# mostek-h.net
KiCad netlist of a schematic drawn in EAGLE
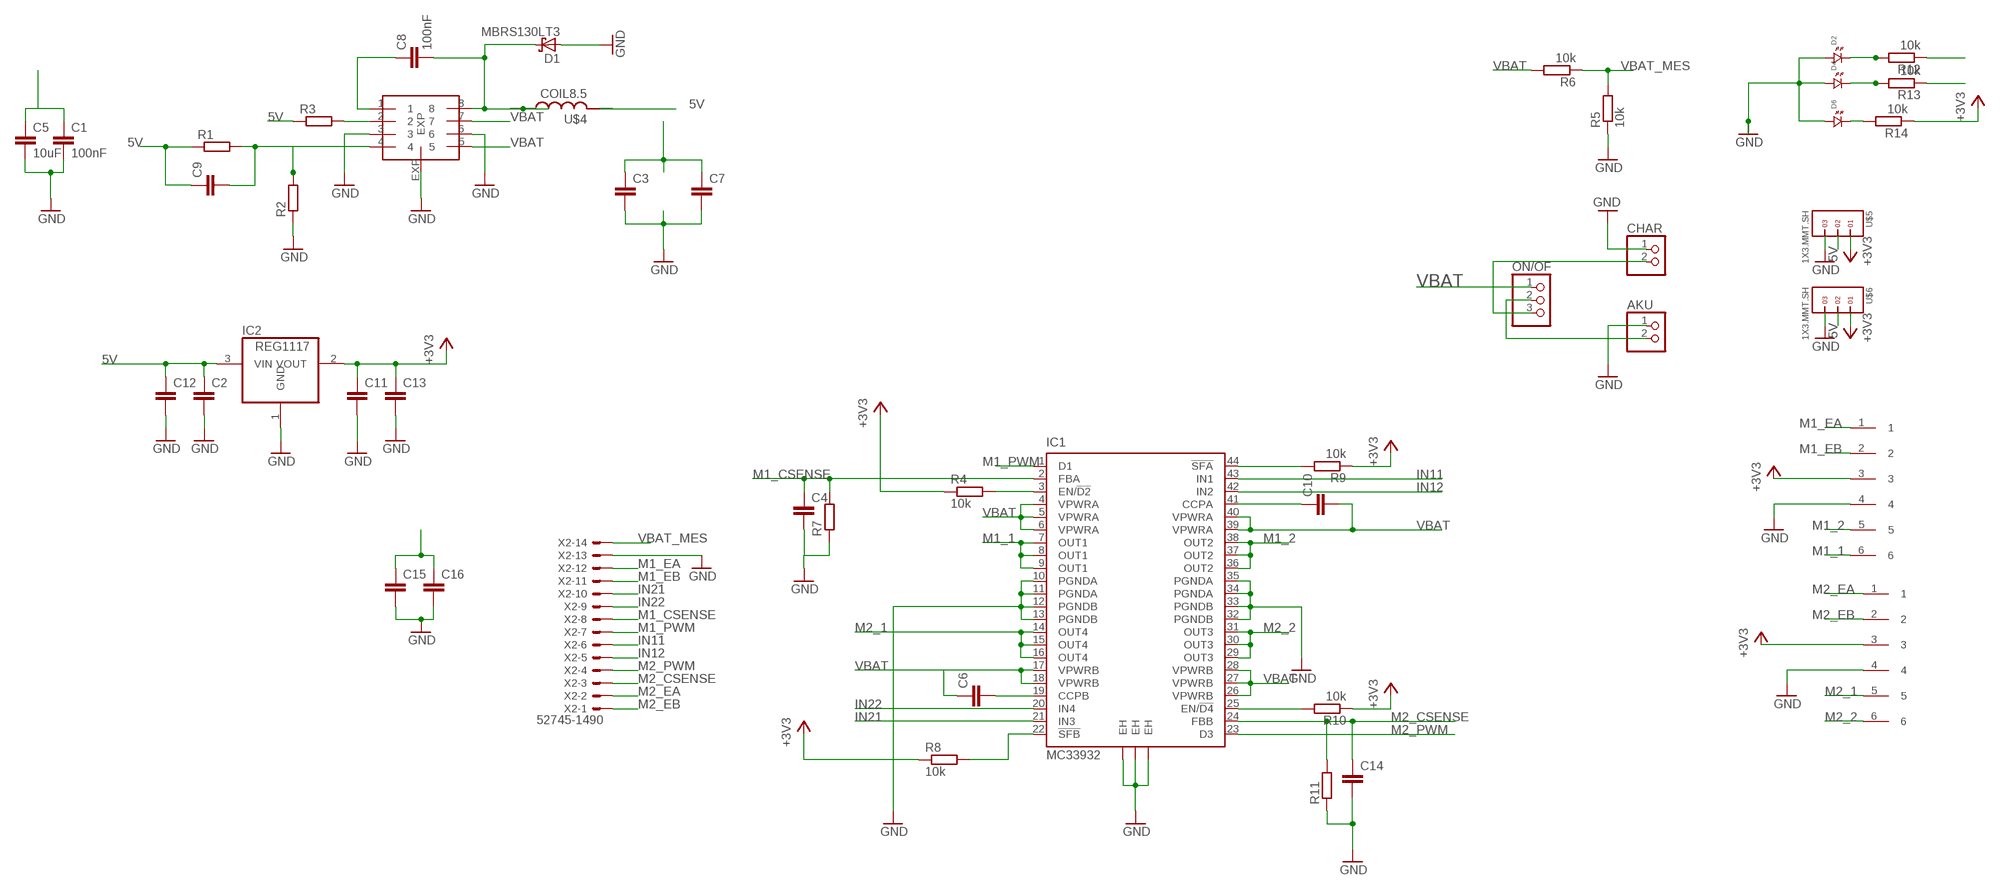
[diagram p0: schematic, sheet 1]

(export (version "E")
  (design (tool "Eeschema 10.0.6"))
  (components
    (comp (ref "AKU")
      (value "PINHD-1X2/90")
      (footprint "eagle-import:1X02_90")
      (libsource (lib "eagle-import") (part "PINHD-1X2/90"))
    )
    (comp (ref "C1")
      (value "100nF")
      (footprint "eagle-import:C1210K")
      (libsource (lib "eagle-import") (part "C-EUC1210K"))
    )
    (comp (ref "C2")
      (value "C-EUC0805")
      (footprint "eagle-import:C0805")
      (libsource (lib "eagle-import") (part "C-EUC0805"))
    )
    (comp (ref "C3")
      (value "C-EUC1210K")
      (footprint "eagle-import:C1210K")
      (libsource (lib "eagle-import") (part "C-EUC1210K"))
    )
    (comp (ref "C4")
      (value "C-EUC0603")
      (footprint "eagle-import:C0603")
      (libsource (lib "eagle-import") (part "C-EUC0603"))
    )
    (comp (ref "C5")
      (value "10uF")
      (footprint "eagle-import:C0603")
      (libsource (lib "eagle-import") (part "C-EUC0603"))
    )
    (comp (ref "C6")
      (value "C-EUC0805")
      (footprint "eagle-import:C0805")
      (libsource (lib "eagle-import") (part "C-EUC0805"))
    )
    (comp (ref "C7")
      (value "C-EUC0603")
      (footprint "eagle-import:C0603")
      (libsource (lib "eagle-import") (part "C-EUC0603"))
    )
    (comp (ref "C8")
      (value "100nF")
      (footprint "eagle-import:C0603")
      (libsource (lib "eagle-import") (part "C-EUC0603"))
    )
    (comp (ref "C9")
      (value "C-EUC0603")
      (footprint "eagle-import:C0603")
      (libsource (lib "eagle-import") (part "C-EUC0603"))
    )
    (comp (ref "C10")
      (value "C-EUC0805")
      (footprint "eagle-import:C0805")
      (libsource (lib "eagle-import") (part "C-EUC0805"))
    )
    (comp (ref "C11")
      (value "C-EUC0805")
      (footprint "eagle-import:C0805")
      (libsource (lib "eagle-import") (part "C-EUC0805"))
    )
    (comp (ref "C12")
      (value "C-EUC1210")
      (footprint "eagle-import:C1210")
      (libsource (lib "eagle-import") (part "C-EUC1210"))
    )
    (comp (ref "C13")
      (value "C-EUC1210")
      (footprint "eagle-import:C1210")
      (libsource (lib "eagle-import") (part "C-EUC1210"))
    )
    (comp (ref "C14")
      (value "C-EUC0603")
      (footprint "eagle-import:C0603")
      (libsource (lib "eagle-import") (part "C-EUC0603"))
    )
    (comp (ref "C15")
      (value "C-EUC1210K")
      (footprint "eagle-import:C1210K")
      (libsource (lib "eagle-import") (part "C-EUC1210K"))
    )
    (comp (ref "C16")
      (value "C-EUC0603")
      (footprint "eagle-import:C0603")
      (libsource (lib "eagle-import") (part "C-EUC0603"))
    )
    (comp (ref "CHAR")
      (value "PINHD-1X2/90")
      (footprint "eagle-import:1X02_90")
      (libsource (lib "eagle-import") (part "PINHD-1X2/90"))
    )
    (comp (ref "D1")
      (value "MBRS130LT3")
      (footprint "eagle-import:SMB")
      (libsource (lib "eagle-import") (part "MBRS130LT3"))
    )
    (comp (ref "D2")
      (value "LED.0805")
      (footprint "eagle-import:0805.LED")
      (libsource (lib "eagle-import") (part "LED.0805"))
    )
    (comp (ref "D4")
      (value "LED.0805")
      (footprint "eagle-import:0805.LED")
      (libsource (lib "eagle-import") (part "LED.0805"))
    )
    (comp (ref "D6")
      (value "LED.0805")
      (footprint "eagle-import:0805.LED")
      (libsource (lib "eagle-import") (part "LED.0805"))
    )
    (comp (ref "IC1")
      (value "MC33932")
      (footprint "eagle-import:HSOP44")
      (fields (field (name "MPN") "MC33932VW"))
      (libsource (lib "eagle-import") (part "MC33932"))
    )
    (comp (ref "IC2")
      (value "REG1117")
      (footprint "eagle-import:SOT223")
      (libsource (lib "eagle-import") (part "REG1117"))
    )
    (comp (ref "ON/OF")
      (value "PINHD-1X3/90")
      (footprint "eagle-import:1X03_90")
      (libsource (lib "eagle-import") (part "PINHD-1X3/90"))
    )
    (comp (ref "R1")
      (value "R-EU_R0603")
      (footprint "eagle-import:R0603")
      (libsource (lib "eagle-import") (part "R-EU_R0603"))
    )
    (comp (ref "R2")
      (value "R-EU_R0603")
      (footprint "eagle-import:R0603")
      (libsource (lib "eagle-import") (part "R-EU_R0603"))
    )
    (comp (ref "R3")
      (value "R-EU_R0603")
      (footprint "eagle-import:R0603")
      (libsource (lib "eagle-import") (part "R-EU_R0603"))
    )
    (comp (ref "R4")
      (value "10k")
      (footprint "eagle-import:R0603")
      (libsource (lib "eagle-import") (part "R-EU_R0603"))
    )
    (comp (ref "R5")
      (value "10k")
      (footprint "eagle-import:R0603")
      (libsource (lib "eagle-import") (part "R-EU_R0603"))
    )
    (comp (ref "R6")
      (value "10k")
      (footprint "eagle-import:R0603")
      (libsource (lib "eagle-import") (part "R-EU_R0603"))
    )
    (comp (ref "R7")
      (value "R-EU_R0603")
      (footprint "eagle-import:R0603")
      (libsource (lib "eagle-import") (part "R-EU_R0603"))
    )
    (comp (ref "R8")
      (value "10k")
      (footprint "eagle-import:R0603")
      (libsource (lib "eagle-import") (part "R-EU_R0603"))
    )
    (comp (ref "R9")
      (value "10k")
      (footprint "eagle-import:R0603")
      (libsource (lib "eagle-import") (part "R-EU_R0603"))
    )
    (comp (ref "R10")
      (value "10k")
      (footprint "eagle-import:R0603")
      (libsource (lib "eagle-import") (part "R-EU_R0603"))
    )
    (comp (ref "R11")
      (value "R-EU_R0603")
      (footprint "eagle-import:R0603")
      (libsource (lib "eagle-import") (part "R-EU_R0603"))
    )
    (comp (ref "R12")
      (value "10k")
      (footprint "eagle-import:R0603")
      (libsource (lib "eagle-import") (part "R-EU_R0603"))
    )
    (comp (ref "R13")
      (value "10k")
      (footprint "eagle-import:R0603")
      (libsource (lib "eagle-import") (part "R-EU_R0603"))
    )
    (comp (ref "R14")
      (value "10k")
      (footprint "eagle-import:R0603")
      (libsource (lib "eagle-import") (part "R-EU_R0603"))
    )
    (comp (ref "U$1")
      (value "PAD_SMD_6X1")
      (footprint "eagle-import:SMD_6X1")
      (libsource (lib "eagle-import") (part "PAD_SMD_6X1"))
    )
    (comp (ref "U$2")
      (value "PAD_SMD_6X1")
      (footprint "eagle-import:SMD_6X1")
      (libsource (lib "eagle-import") (part "PAD_SMD_6X1"))
    )
    (comp (ref "U$3")
      (value "ST1S14")
      (footprint "eagle-import:HSOP8")
      (libsource (lib "eagle-import") (part "ST1S14"))
    )
    (comp (ref "U$4")
      (value "COIL8.5")
      (footprint "eagle-import:COIL1")
      (libsource (lib "eagle-import") (part "COIL8.5"))
    )
    (comp (ref "U$5")
      (value "1X3.MMT.SH")
      (footprint "eagle-import:1X3_MMT.103.01.X.SH")
      (libsource (lib "eagle-import") (part "1X3.MMT.SH"))
    )
    (comp (ref "U$6")
      (value "1X3.MMT.SH")
      (footprint "eagle-import:1X3_MMT.103.01.X.SH")
      (libsource (lib "eagle-import") (part "1X3.MMT.SH"))
    )
    (comp (ref "X2")
      (value "52745-1490")
      (footprint "eagle-import:52745-1490")
      (fields (field (name "MF") "WALDOM/MOLEX"))
      (libsource (lib "eagle-import") (part "52745-1490"))
    )
  )
  (nets
    (net (code "1") (name "+3V3") (class "Default")
      (node (ref "C11") (pin "1") (pinfunction "1_1") (pintype "passive"))
      (node (ref "C13") (pin "1") (pinfunction "1_1") (pintype "passive"))
      (node (ref "IC2") (pin "2") (pinfunction "VOUT_2") (pintype "output"))
      (node (ref "R10") (pin "1") (pinfunction "1_1") (pintype "passive"))
      (node (ref "R14") (pin "1") (pinfunction "1_1") (pintype "passive"))
      (node (ref "R4") (pin "1") (pinfunction "1_1") (pintype "passive"))
      (node (ref "R8") (pin "1") (pinfunction "1_1") (pintype "passive"))
      (node (ref "R9") (pin "1") (pinfunction "1_1") (pintype "passive"))
      (node (ref "U$1") (pin "3") (pinfunction "3_3") (pintype "bidirectional"))
      (node (ref "U$2") (pin "3") (pinfunction "3_3") (pintype "bidirectional"))
      (node (ref "U$5") (pin "1") (pinfunction "1_1") (pintype "bidirectional"))
      (node (ref "U$6") (pin "1") (pinfunction "1_1") (pintype "bidirectional"))
    )
    (net (code "2") (name "/5V") (class "Default")
      (node (ref "C12") (pin "1") (pinfunction "1_1") (pintype "passive"))
      (node (ref "C2") (pin "1") (pinfunction "1_1") (pintype "passive"))
      (node (ref "C3") (pin "1") (pinfunction "1_1") (pintype "passive"))
      (node (ref "C7") (pin "1") (pinfunction "1_1") (pintype "passive"))
      (node (ref "C9") (pin "1") (pinfunction "1_1") (pintype "passive"))
      (node (ref "IC2") (pin "3") (pinfunction "VIN_3") (pintype "input"))
      (node (ref "R1") (pin "1") (pinfunction "1_1") (pintype "passive"))
      (node (ref "R13") (pin "1") (pinfunction "1_1") (pintype "passive"))
      (node (ref "R3") (pin "1") (pinfunction "1_1") (pintype "passive"))
      (node (ref "U$4") (pin "2") (pinfunction "2_2") (pintype "passive"))
      (node (ref "U$5") (pin "2") (pinfunction "2_2") (pintype "bidirectional"))
      (node (ref "U$6") (pin "2") (pinfunction "2_2") (pintype "bidirectional"))
    )
    (net (code "3") (name "/IN11") (class "Default")
      (node (ref "IC1") (pin "43") (pinfunction "IN1_43") (pintype "input"))
      (node (ref "X2") (pin "6") (pinfunction "S_6") (pintype "passive"))
    )
    (net (code "4") (name "/IN12") (class "Default")
      (node (ref "IC1") (pin "42") (pinfunction "IN2_42") (pintype "input"))
      (node (ref "X2") (pin "5") (pinfunction "S_5") (pintype "passive"))
    )
    (net (code "5") (name "/IN21") (class "Default")
      (node (ref "IC1") (pin "21") (pinfunction "IN3_21") (pintype "input"))
      (node (ref "X2") (pin "10") (pinfunction "S_10") (pintype "passive"))
    )
    (net (code "6") (name "/IN22") (class "Default")
      (node (ref "IC1") (pin "20") (pinfunction "IN4_20") (pintype "input"))
      (node (ref "X2") (pin "9") (pinfunction "S_9") (pintype "passive"))
    )
    (net (code "7") (name "/M1_1") (class "Default")
      (node (ref "IC1") (pin "7") (pinfunction "OUT1_7") (pintype "output"))
      (node (ref "IC1") (pin "8") (pinfunction "OUT1_8") (pintype "passive"))
      (node (ref "IC1") (pin "9") (pinfunction "OUT1_9") (pintype "passive"))
      (node (ref "U$1") (pin "6") (pinfunction "6_6") (pintype "bidirectional"))
    )
    (net (code "8") (name "/M1_2") (class "Default")
      (node (ref "IC1") (pin "36") (pinfunction "OUT2_36") (pintype "output"))
      (node (ref "IC1") (pin "37") (pinfunction "OUT2_37") (pintype "passive"))
      (node (ref "IC1") (pin "38") (pinfunction "OUT2_38") (pintype "passive"))
      (node (ref "U$1") (pin "5") (pinfunction "5_5") (pintype "bidirectional"))
    )
    (net (code "9") (name "/M1_CSENSE") (class "Default")
      (node (ref "C4") (pin "1") (pinfunction "1_1") (pintype "passive"))
      (node (ref "IC1") (pin "2") (pinfunction "FBA_2") (pintype "output"))
      (node (ref "R7") (pin "2") (pinfunction "2_2") (pintype "passive"))
      (node (ref "X2") (pin "8") (pinfunction "S_8") (pintype "passive"))
    )
    (net (code "10") (name "/M1_EA") (class "Default")
      (node (ref "U$1") (pin "1") (pinfunction "1_1") (pintype "bidirectional"))
      (node (ref "X2") (pin "12") (pinfunction "S_12") (pintype "passive"))
    )
    (net (code "11") (name "/M1_EB") (class "Default")
      (node (ref "U$1") (pin "2") (pinfunction "2_2") (pintype "bidirectional"))
      (node (ref "X2") (pin "11") (pinfunction "S_11") (pintype "passive"))
    )
    (net (code "12") (name "/M1_PWM") (class "Default")
      (node (ref "IC1") (pin "1") (pinfunction "D1_1") (pintype "input"))
      (node (ref "X2") (pin "7") (pinfunction "S_7") (pintype "passive"))
    )
    (net (code "13") (name "/M2_1") (class "Default")
      (node (ref "IC1") (pin "14") (pinfunction "OUT4_14") (pintype "output"))
      (node (ref "IC1") (pin "15") (pinfunction "OUT4_15") (pintype "passive"))
      (node (ref "IC1") (pin "16") (pinfunction "OUT4_16") (pintype "passive"))
      (node (ref "U$2") (pin "5") (pinfunction "5_5") (pintype "bidirectional"))
    )
    (net (code "14") (name "/M2_2") (class "Default")
      (node (ref "IC1") (pin "29") (pinfunction "OUT3_29") (pintype "output"))
      (node (ref "IC1") (pin "30") (pinfunction "OUT3_30") (pintype "passive"))
      (node (ref "IC1") (pin "31") (pinfunction "OUT3_31") (pintype "passive"))
      (node (ref "U$2") (pin "6") (pinfunction "6_6") (pintype "bidirectional"))
    )
    (net (code "15") (name "/M2_CSENSE") (class "Default")
      (node (ref "C14") (pin "1") (pinfunction "1_1") (pintype "passive"))
      (node (ref "IC1") (pin "24") (pinfunction "FBB_24") (pintype "output"))
      (node (ref "R11") (pin "2") (pinfunction "2_2") (pintype "passive"))
      (node (ref "X2") (pin "3") (pinfunction "S_3") (pintype "passive"))
    )
    (net (code "16") (name "/M2_EA") (class "Default")
      (node (ref "U$2") (pin "1") (pinfunction "1_1") (pintype "bidirectional"))
      (node (ref "X2") (pin "2") (pinfunction "S_2") (pintype "passive"))
    )
    (net (code "17") (name "/M2_EB") (class "Default")
      (node (ref "U$2") (pin "2") (pinfunction "2_2") (pintype "bidirectional"))
      (node (ref "X2") (pin "1") (pinfunction "S_1") (pintype "passive"))
    )
    (net (code "18") (name "/M2_PWM") (class "Default")
      (node (ref "IC1") (pin "23") (pinfunction "D3_23") (pintype "input"))
      (node (ref "X2") (pin "4") (pinfunction "S_4") (pintype "passive"))
    )
    (net (code "19") (name "/VBAT") (class "Default")
      (node (ref "C1") (pin "1") (pinfunction "1_1") (pintype "passive"))
      (node (ref "C10") (pin "2") (pinfunction "2_2") (pintype "passive"))
      (node (ref "C15") (pin "1") (pinfunction "1_1") (pintype "passive"))
      (node (ref "C16") (pin "1") (pinfunction "1_1") (pintype "passive"))
      (node (ref "C5") (pin "1") (pinfunction "1_1") (pintype "passive"))
      (node (ref "C6") (pin "1") (pinfunction "1_1") (pintype "passive"))
      (node (ref "IC1") (pin "17") (pinfunction "VPWRB_17") (pintype "input"))
      (node (ref "IC1") (pin "18") (pinfunction "VPWRB_18") (pintype "input"))
      (node (ref "IC1") (pin "26") (pinfunction "VPWRB_26") (pintype "input"))
      (node (ref "IC1") (pin "27") (pinfunction "VPWRB_27") (pintype "input"))
      (node (ref "IC1") (pin "28") (pinfunction "VPWRB_28") (pintype "input"))
      (node (ref "IC1") (pin "39") (pinfunction "VPWRA_39") (pintype "input"))
      (node (ref "IC1") (pin "4") (pinfunction "VPWRA_4") (pintype "input"))
      (node (ref "IC1") (pin "40") (pinfunction "VPWRA_40") (pintype "input"))
      (node (ref "IC1") (pin "5") (pinfunction "VPWRA_5") (pintype "input"))
      (node (ref "IC1") (pin "6") (pinfunction "VPWRA_6") (pintype "input"))
      (node (ref "ON/OF") (pin "1") (pinfunction "1_1") (pintype "passive"))
      (node (ref "R12") (pin "1") (pinfunction "1_1") (pintype "passive"))
      (node (ref "R6") (pin "2") (pinfunction "2_2") (pintype "passive"))
      (node (ref "U$3") (pin "5") (pinfunction "5_5") (pintype "bidirectional"))
      (node (ref "U$3") (pin "7") (pinfunction "7_7") (pintype "bidirectional"))
    )
    (net (code "20") (name "/VBAT_MES") (class "Default")
      (node (ref "R5") (pin "2") (pinfunction "2_2") (pintype "passive"))
      (node (ref "R6") (pin "1") (pinfunction "1_1") (pintype "passive"))
      (node (ref "X2") (pin "14") (pinfunction "S_14") (pintype "passive"))
    )
    (net (code "21") (name "GND") (class "Default")
      (node (ref "AKU") (pin "1") (pinfunction "1_1") (pintype "passive"))
      (node (ref "C1") (pin "2") (pinfunction "2_2") (pintype "passive"))
      (node (ref "C11") (pin "2") (pinfunction "2_2") (pintype "passive"))
      (node (ref "C12") (pin "2") (pinfunction "2_2") (pintype "passive"))
      (node (ref "C13") (pin "2") (pinfunction "2_2") (pintype "passive"))
      (node (ref "C14") (pin "2") (pinfunction "2_2") (pintype "passive"))
      (node (ref "C15") (pin "2") (pinfunction "2_2") (pintype "passive"))
      (node (ref "C16") (pin "2") (pinfunction "2_2") (pintype "passive"))
      (node (ref "C2") (pin "2") (pinfunction "2_2") (pintype "passive"))
      (node (ref "C3") (pin "2") (pinfunction "2_2") (pintype "passive"))
      (node (ref "C4") (pin "2") (pinfunction "2_2") (pintype "passive"))
      (node (ref "C5") (pin "2") (pinfunction "2_2") (pintype "passive"))
      (node (ref "C7") (pin "2") (pinfunction "2_2") (pintype "passive"))
      (node (ref "CHAR") (pin "1") (pinfunction "1_1") (pintype "passive"))
      (node (ref "D1") (pin "A") (pinfunction "A_A") (pintype "passive"))
      (node (ref "D2") (pin "P$1") (pinfunction "1_P$1") (pintype "bidirectional"))
      (node (ref "D4") (pin "P$1") (pinfunction "1_P$1") (pintype "bidirectional"))
      (node (ref "D6") (pin "P$1") (pinfunction "1_P$1") (pintype "bidirectional"))
      (node (ref "IC1") (pin "10") (pinfunction "PGNDA_10") (pintype "power_in"))
      (node (ref "IC1") (pin "11") (pinfunction "PGNDA_11") (pintype "power_in"))
      (node (ref "IC1") (pin "12") (pinfunction "PGNDB_12") (pintype "power_in"))
      (node (ref "IC1") (pin "13") (pinfunction "PGNDB_13") (pintype "power_in"))
      (node (ref "IC1") (pin "32") (pinfunction "PGNDB_32") (pintype "power_in"))
      (node (ref "IC1") (pin "33") (pinfunction "PGNDB_33") (pintype "power_in"))
      (node (ref "IC1") (pin "34") (pinfunction "PGNDA_34") (pintype "power_in"))
      (node (ref "IC1") (pin "35") (pinfunction "PGNDA_35") (pintype "power_in"))
      (node (ref "IC1") (pin "EH@1") (pinfunction "EH_EH@1") (pintype "passive"))
      (node (ref "IC1") (pin "EH@2") (pinfunction "EH_EH@2") (pintype "passive"))
      (node (ref "IC1") (pin "EH@3") (pinfunction "EH_EH@3") (pintype "passive"))
      (node (ref "IC2") (pin "1") (pinfunction "GND_1") (pintype "power_in"))
      (node (ref "R11") (pin "1") (pinfunction "1_1") (pintype "passive"))
      (node (ref "R2") (pin "1") (pinfunction "1_1") (pintype "passive"))
      (node (ref "R5") (pin "1") (pinfunction "1_1") (pintype "passive"))
      (node (ref "R7") (pin "1") (pinfunction "1_1") (pintype "passive"))
      (node (ref "U$1") (pin "4") (pinfunction "4_4") (pintype "bidirectional"))
      (node (ref "U$2") (pin "4") (pinfunction "4_4") (pintype "bidirectional"))
      (node (ref "U$3") (pin "3") (pinfunction "3_3") (pintype "bidirectional"))
      (node (ref "U$3") (pin "6") (pinfunction "6_6") (pintype "bidirectional"))
      (node (ref "U$3") (pin "EXP") (pinfunction "EXP_EXP") (pintype "bidirectional"))
      (node (ref "U$5") (pin "3") (pinfunction "3_3") (pintype "bidirectional"))
      (node (ref "U$6") (pin "3") (pinfunction "3_3") (pintype "bidirectional"))
      (node (ref "X2") (pin "13") (pinfunction "S_13") (pintype "passive"))
    )
    (net (code "22") (name "Net-(AKU-Pad2)") (class "Default")
      (node (ref "AKU") (pin "2") (pinfunction "2_2") (pintype "passive"))
      (node (ref "ON/OF") (pin "2") (pinfunction "2_2") (pintype "passive"))
    )
    (net (code "23") (name "Net-(C8-Pad1)") (class "Default")
      (node (ref "C8") (pin "1") (pinfunction "1_1") (pintype "passive"))
      (node (ref "U$3") (pin "1") (pinfunction "1_1") (pintype "bidirectional"))
    )
    (net (code "24") (name "Net-(C8-Pad2)") (class "Default")
      (node (ref "C8") (pin "2") (pinfunction "2_2") (pintype "passive"))
      (node (ref "D1") (pin "C") (pinfunction "C_C") (pintype "passive"))
      (node (ref "U$3") (pin "8") (pinfunction "8_8") (pintype "bidirectional"))
      (node (ref "U$4") (pin "1") (pinfunction "1_1") (pintype "passive"))
    )
    (net (code "25") (name "Net-(C9-Pad2)") (class "Default")
      (node (ref "C9") (pin "2") (pinfunction "2_2") (pintype "passive"))
      (node (ref "R1") (pin "2") (pinfunction "2_2") (pintype "passive"))
      (node (ref "R2") (pin "2") (pinfunction "2_2") (pintype "passive"))
      (node (ref "U$3") (pin "4") (pinfunction "4_4") (pintype "bidirectional"))
    )
    (net (code "26") (name "Net-(CHAR-Pad2)") (class "Default")
      (node (ref "CHAR") (pin "2") (pinfunction "2_2") (pintype "passive"))
      (node (ref "ON/OF") (pin "3") (pinfunction "3_3") (pintype "passive"))
    )
    (net (code "27") (name "Net-(D2-2)") (class "Default")
      (node (ref "D2") (pin "P$2") (pinfunction "2_P$2") (pintype "bidirectional"))
      (node (ref "R12") (pin "2") (pinfunction "2_2") (pintype "passive"))
    )
    (net (code "28") (name "Net-(D4-2)") (class "Default")
      (node (ref "D4") (pin "P$2") (pinfunction "2_P$2") (pintype "bidirectional"))
      (node (ref "R13") (pin "2") (pinfunction "2_2") (pintype "passive"))
    )
    (net (code "29") (name "Net-(D6-2)") (class "Default")
      (node (ref "D6") (pin "P$2") (pinfunction "2_P$2") (pintype "bidirectional"))
      (node (ref "R14") (pin "2") (pinfunction "2_2") (pintype "passive"))
    )
    (net (code "30") (name "Net-(IC1-CCPA)") (class "Default")
      (node (ref "C10") (pin "1") (pinfunction "1_1") (pintype "passive"))
      (node (ref "IC1") (pin "41") (pinfunction "CCPA_41") (pintype "output"))
    )
    (net (code "31") (name "Net-(IC1-CCPB)") (class "Default")
      (node (ref "C6") (pin "2") (pinfunction "2_2") (pintype "passive"))
      (node (ref "IC1") (pin "19") (pinfunction "CCPB_19") (pintype "output"))
    )
    (net (code "32") (name "Net-(IC1-EN{slash}~{D2})") (class "Default")
      (node (ref "IC1") (pin "3") (pinfunction "EN/~{D2}_3") (pintype "input"))
      (node (ref "R4") (pin "2") (pinfunction "2_2") (pintype "passive"))
    )
    (net (code "33") (name "Net-(IC1-EN{slash}~{D4})") (class "Default")
      (node (ref "IC1") (pin "25") (pinfunction "EN/~{D4}_25") (pintype "input"))
      (node (ref "R10") (pin "2") (pinfunction "2_2") (pintype "passive"))
    )
    (net (code "34") (name "Net-(IC1-~{SFA})") (class "Default")
      (node (ref "IC1") (pin "44") (pinfunction "~{SFA}_44") (pintype "open_collector"))
      (node (ref "R9") (pin "2") (pinfunction "2_2") (pintype "passive"))
    )
    (net (code "35") (name "Net-(IC1-~{SFB})") (class "Default")
      (node (ref "IC1") (pin "22") (pinfunction "~{SFB}_22") (pintype "open_collector"))
      (node (ref "R8") (pin "2") (pinfunction "2_2") (pintype "passive"))
    )
    (net (code "36") (name "Net-(R3-Pad2)") (class "Default")
      (node (ref "R3") (pin "2") (pinfunction "2_2") (pintype "passive"))
      (node (ref "U$3") (pin "2") (pinfunction "2_2") (pintype "bidirectional"))
    )
  )
)
